# Daughter_Board.net
KiCad netlist of a schematic drawn in EAGLE
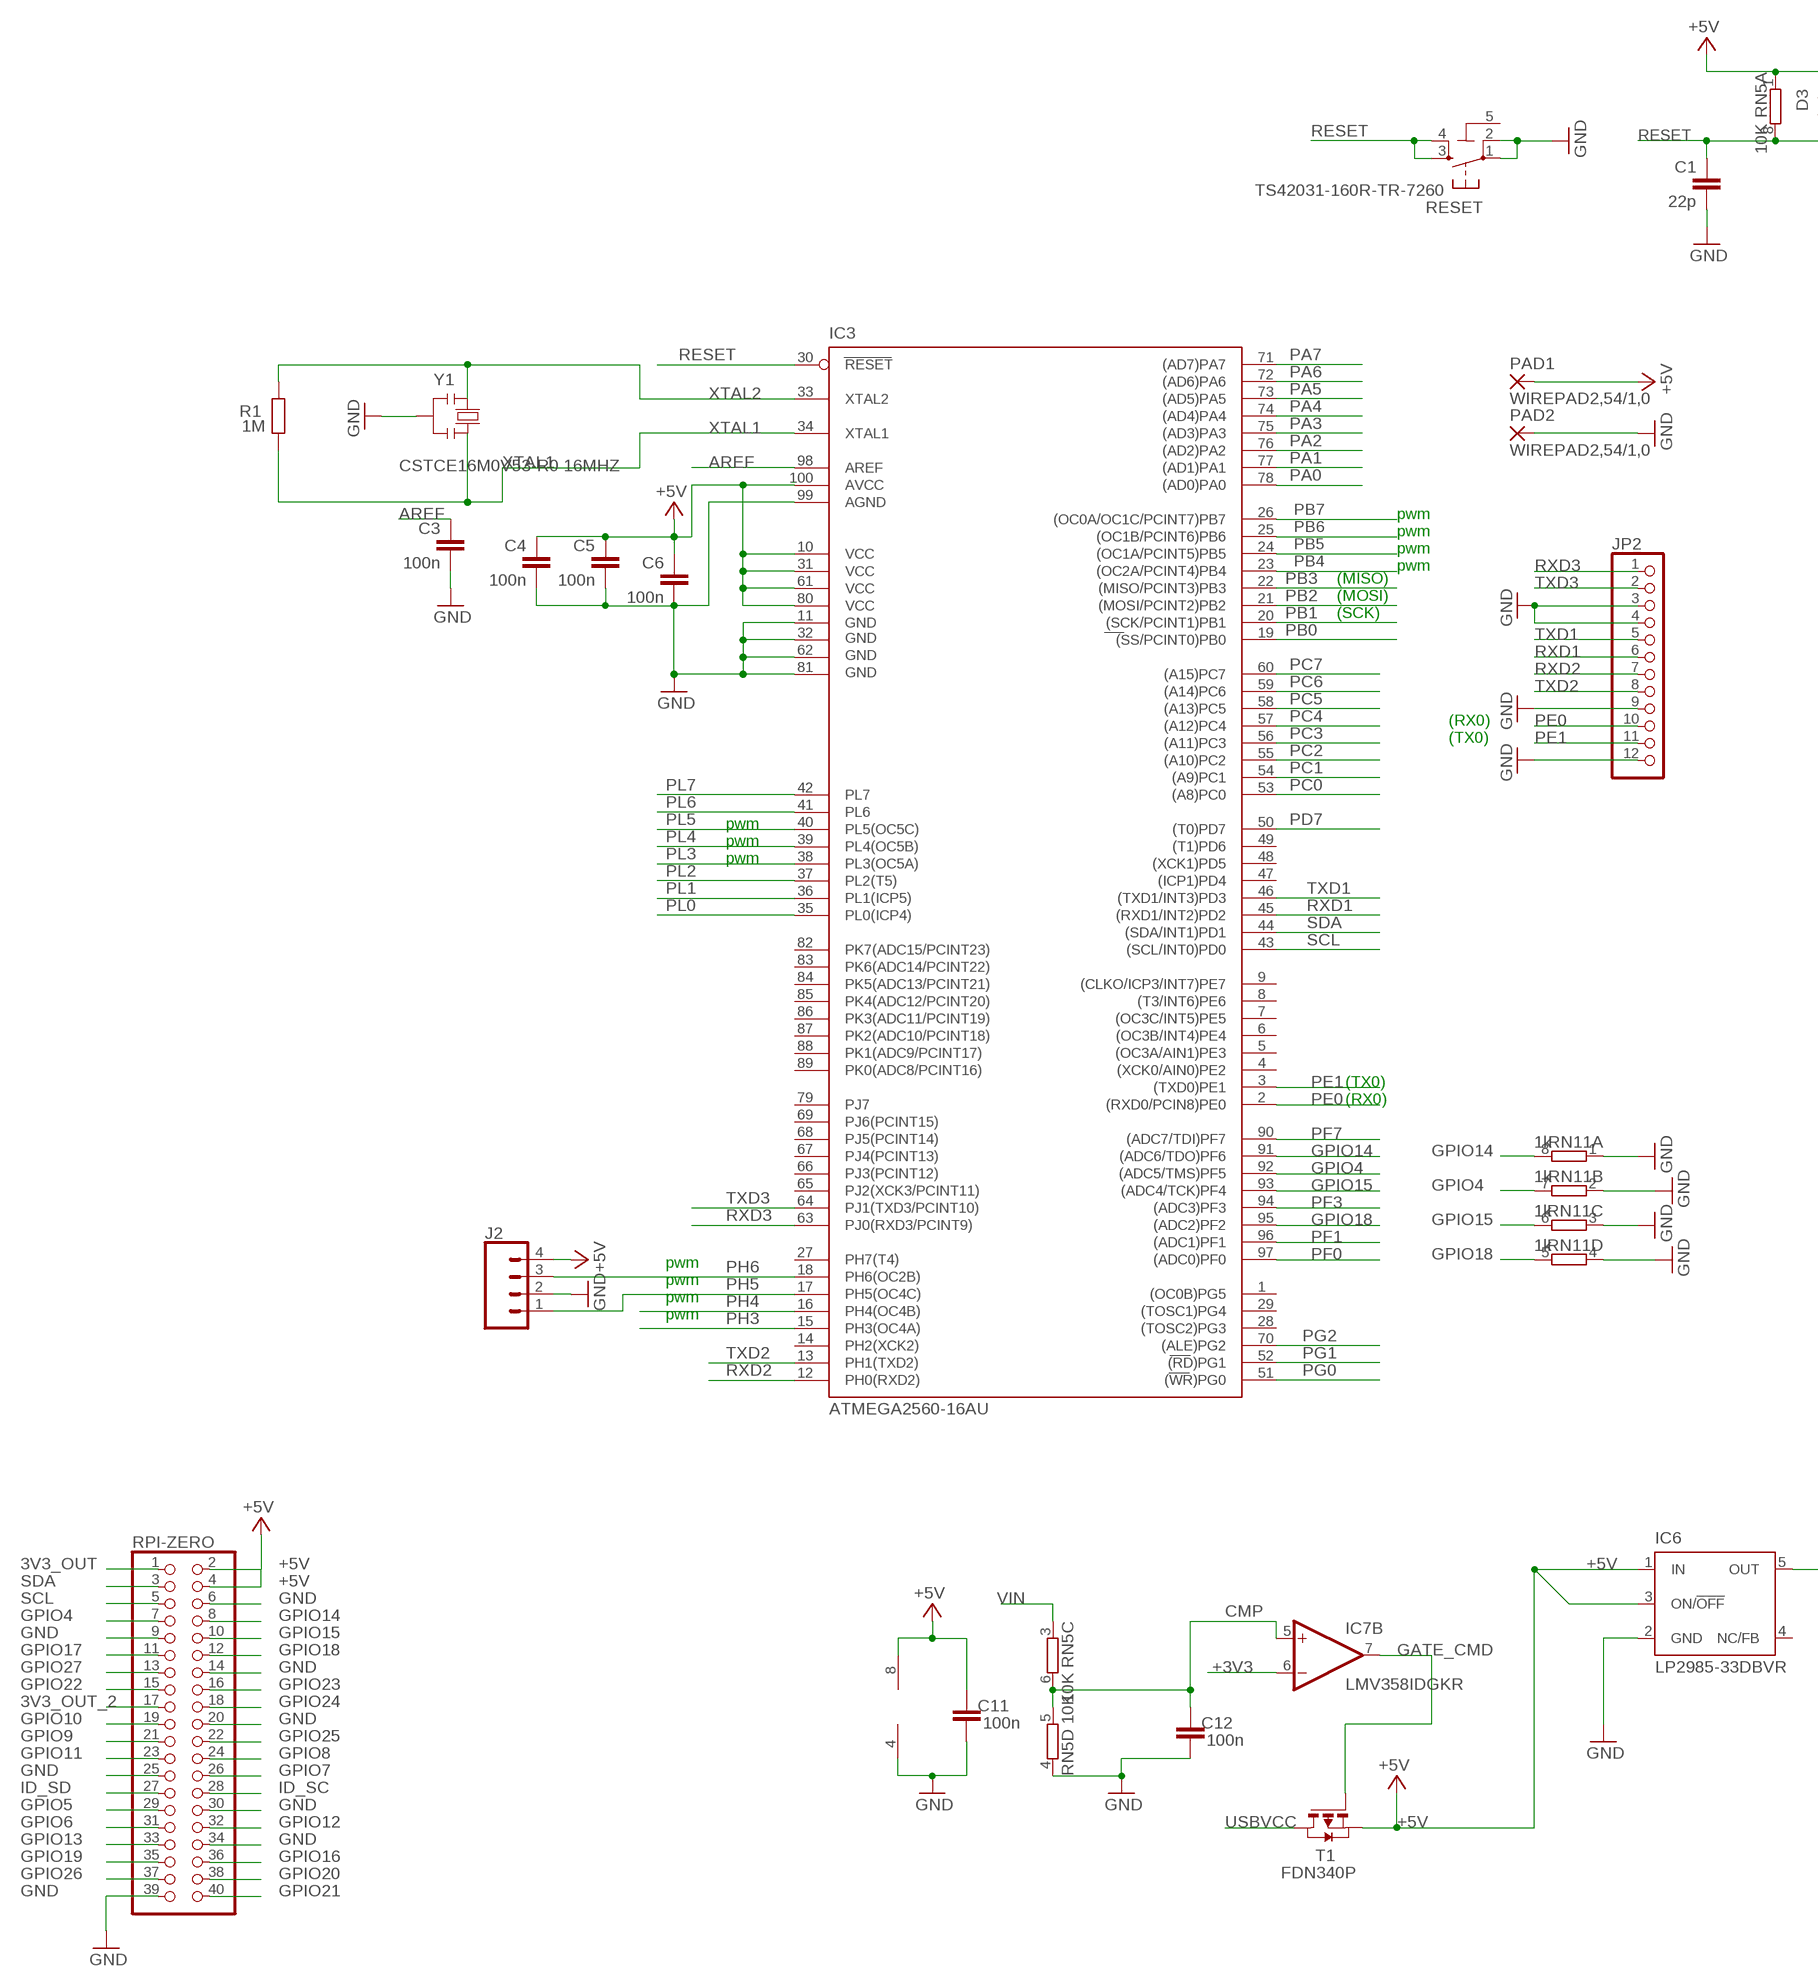
[diagram p0: schematic, sheet 1, part 1 of 2]
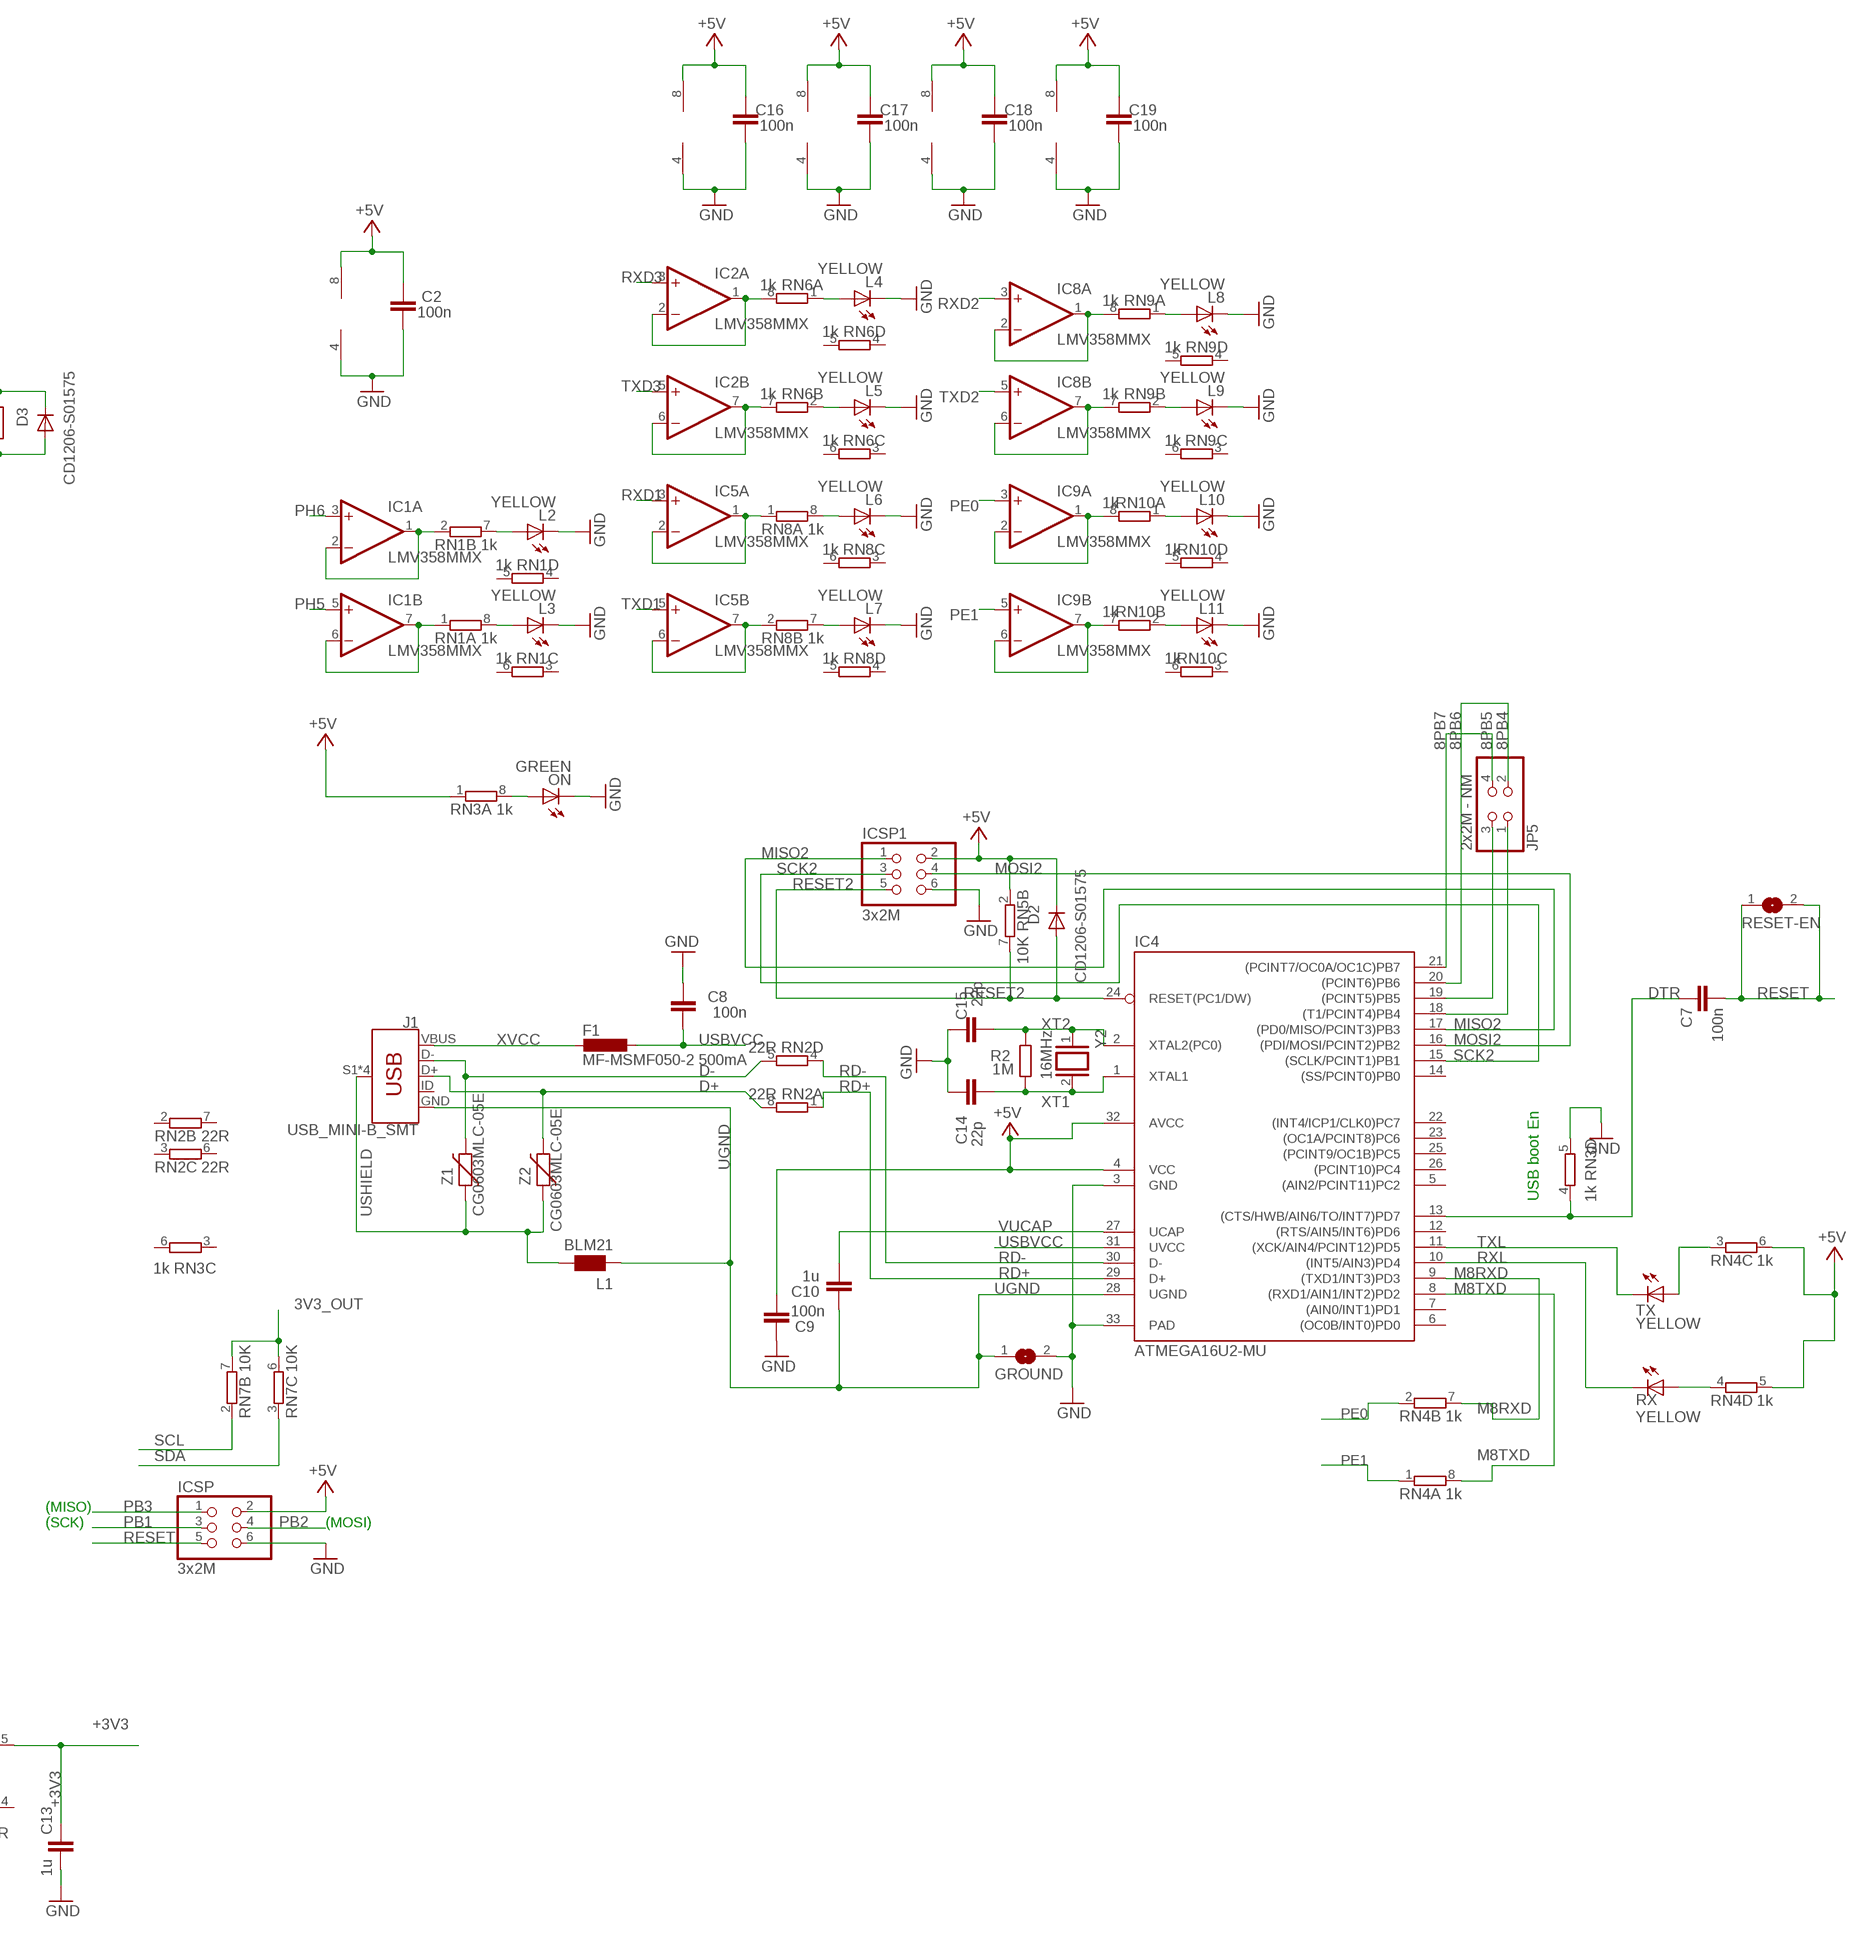
[diagram p1: schematic, sheet 1, part 2 of 2]

(export (version "E")
  (design (tool "Eeschema 10.0.6"))
  (components
    (comp (ref "C1")
      (value "22p")
      (footprint "eagle-import:C0603-ROUND")
      (libsource (lib "eagle-import") (part "C-EU0603-RND"))
    )
    (comp (ref "C2")
      (value "100n")
      (footprint "eagle-import:C0603-ROUND")
      (libsource (lib "eagle-import") (part "C-EU0603-RND"))
    )
    (comp (ref "C3")
      (value "100n")
      (footprint "eagle-import:C0603-ROUND")
      (libsource (lib "eagle-import") (part "C-EU0603-RND"))
    )
    (comp (ref "C4")
      (value "100n")
      (footprint "eagle-import:C0603-ROUND")
      (libsource (lib "eagle-import") (part "C-EU0603-RND"))
    )
    (comp (ref "C5")
      (value "100n")
      (footprint "eagle-import:C0603-ROUND")
      (libsource (lib "eagle-import") (part "C-EU0603-RND"))
    )
    (comp (ref "C6")
      (value "100n")
      (footprint "eagle-import:C0603-ROUND")
      (libsource (lib "eagle-import") (part "C-EU0603-RND"))
    )
    (comp (ref "C7")
      (value "100n")
      (footprint "eagle-import:C0603-ROUND")
      (libsource (lib "eagle-import") (part "C-EU0603-RND"))
    )
    (comp (ref "C8")
      (value "100n")
      (footprint "eagle-import:C0603-ROUND")
      (libsource (lib "eagle-import") (part "C-EU0603-RND"))
    )
    (comp (ref "C9")
      (value "100n")
      (footprint "eagle-import:C0603-ROUND")
      (libsource (lib "eagle-import") (part "C-EU0603-RND"))
    )
    (comp (ref "C10")
      (value "1u")
      (footprint "eagle-import:C0603-ROUND")
      (libsource (lib "eagle-import") (part "C-EU0603-RND"))
    )
    (comp (ref "C11")
      (value "100n")
      (footprint "eagle-import:C0603-ROUND")
      (libsource (lib "eagle-import") (part "C-EU0603-RND"))
    )
    (comp (ref "C12")
      (value "100n")
      (footprint "eagle-import:C0603-ROUND")
      (libsource (lib "eagle-import") (part "C-EU0603-RND"))
    )
    (comp (ref "C13")
      (value "1u")
      (footprint "eagle-import:C0603-ROUND")
      (libsource (lib "eagle-import") (part "C-EU0603-RND"))
    )
    (comp (ref "C14")
      (value "22p")
      (footprint "eagle-import:C0603-ROUND")
      (libsource (lib "eagle-import") (part "C-EU0603-RND"))
    )
    (comp (ref "C15")
      (value "22p")
      (footprint "eagle-import:C0603-ROUND")
      (libsource (lib "eagle-import") (part "C-EU0603-RND"))
    )
    (comp (ref "C16")
      (value "100n")
      (footprint "eagle-import:C0603-ROUND")
      (libsource (lib "eagle-import") (part "C-EU0603-RND"))
    )
    (comp (ref "C17")
      (value "100n")
      (footprint "eagle-import:C0603-ROUND")
      (libsource (lib "eagle-import") (part "C-EU0603-RND"))
    )
    (comp (ref "C18")
      (value "100n")
      (footprint "eagle-import:C0603-ROUND")
      (libsource (lib "eagle-import") (part "C-EU0603-RND"))
    )
    (comp (ref "C19")
      (value "100n")
      (footprint "eagle-import:C0603-ROUND")
      (libsource (lib "eagle-import") (part "C-EU0603-RND"))
    )
    (comp (ref "D2")
      (value "CD1206-S01575")
      (footprint "eagle-import:MINIMELF")
      (libsource (lib "eagle-import") (part "DIODE-MINIMELF"))
    )
    (comp (ref "D3")
      (value "CD1206-S01575")
      (footprint "eagle-import:MINIMELF")
      (libsource (lib "eagle-import") (part "DIODE-MINIMELF"))
    )
    (comp (ref "F1")
      (value "MF-MSMF050-2 500mA")
      (footprint "eagle-import:L1812")
      (libsource (lib "eagle-import") (part "L-EUL1812"))
    )
    (comp (ref "GROUND")
      (value "SJ")
      (footprint "eagle-import:SJ")
      (libsource (lib "eagle-import") (part "SJ"))
    )
    (comp (ref "IC1")
      (value "LMV358MMX")
      (footprint "eagle-import:MSOP08")
      (libsource (lib "eagle-import") (part "linear_262_LMV358?MMX"))
    )
    (comp (ref "IC2")
      (value "LMV358MMX")
      (footprint "eagle-import:MSOP08")
      (libsource (lib "eagle-import") (part "linear_262_LMV358?MMX"))
    )
    (comp (ref "IC3")
      (value "ATMEGA2560-16AU")
      (footprint "eagle-import:TQFP100")
      (libsource (lib "eagle-import") (part "ATMEGA2560AU2560-16"))
    )
    (comp (ref "IC4")
      (value "ATMEGA16U2-MU")
      (footprint "eagle-import:MLF32")
      (libsource (lib "eagle-import") (part "ATMEGA16U2-MU"))
    )
    (comp (ref "IC5")
      (value "LMV358MMX")
      (footprint "eagle-import:MSOP08")
      (libsource (lib "eagle-import") (part "linear_262_LMV358?MMX"))
    )
    (comp (ref "IC6")
      (value "LP2985-33DBVR")
      (footprint "eagle-import:SOT23-DBV")
      (libsource (lib "eagle-import") (part "LP2985-XXDBVR33"))
    )
    (comp (ref "IC7")
      (value "LMV358IDGKR")
      (footprint "eagle-import:MSOP08")
      (libsource (lib "eagle-import") (part "LMV358?MMX"))
    )
    (comp (ref "IC8")
      (value "LMV358MMX")
      (footprint "eagle-import:MSOP08")
      (libsource (lib "eagle-import") (part "linear_262_LMV358?MMX"))
    )
    (comp (ref "IC9")
      (value "LMV358MMX")
      (footprint "eagle-import:MSOP08")
      (libsource (lib "eagle-import") (part "linear_262_LMV358?MMX"))
    )
    (comp (ref "ICSP")
      (value "3x2M")
      (footprint "eagle-import:2X03")
      (libsource (lib "eagle-import") (part "PINHD-2X3"))
    )
    (comp (ref "ICSP1")
      (value "3x2M")
      (footprint "eagle-import:2X03")
      (libsource (lib "eagle-import") (part "PINHD-2X3"))
    )
    (comp (ref "J1")
      (value "USB_MINI-B_SMT")
      (footprint "eagle-import:USB-MINIB")
      (libsource (lib "eagle-import") (part "USB_MINI-B_SMT"))
    )
    (comp (ref "J2")
      (value "CONN_04")
      (footprint "eagle-import:1X04")
      (libsource (lib "eagle-import") (part "CONN_04"))
    )
    (comp (ref "JP2")
      (value "PINHD-1X12-CB")
      (footprint "eagle-import:1X12-CB")
      (libsource (lib "eagle-import") (part "PINHD-1X12-CB"))
    )
    (comp (ref "JP5")
      (value "2x2M - NM")
      (footprint "eagle-import:2X02")
      (libsource (lib "eagle-import") (part "PINHD-2X2"))
    )
    (comp (ref "L1")
      (value "BLM21")
      (footprint "eagle-import:0805")
      (libsource (lib "eagle-import") (part "WE-CBF_0805"))
    )
    (comp (ref "L2")
      (value "YELLOW")
      (footprint "eagle-import:CHIP-LED0805")
      (libsource (lib "eagle-import") (part "LEDCHIP-LED0805"))
    )
    (comp (ref "L3")
      (value "YELLOW")
      (footprint "eagle-import:CHIP-LED0805")
      (libsource (lib "eagle-import") (part "LEDCHIP-LED0805"))
    )
    (comp (ref "L4")
      (value "YELLOW")
      (footprint "eagle-import:CHIP-LED0805")
      (libsource (lib "eagle-import") (part "LEDCHIP-LED0805"))
    )
    (comp (ref "L5")
      (value "YELLOW")
      (footprint "eagle-import:CHIP-LED0805")
      (libsource (lib "eagle-import") (part "LEDCHIP-LED0805"))
    )
    (comp (ref "L6")
      (value "YELLOW")
      (footprint "eagle-import:CHIP-LED0805")
      (libsource (lib "eagle-import") (part "LEDCHIP-LED0805"))
    )
    (comp (ref "L7")
      (value "YELLOW")
      (footprint "eagle-import:CHIP-LED0805")
      (libsource (lib "eagle-import") (part "LEDCHIP-LED0805"))
    )
    (comp (ref "L8")
      (value "YELLOW")
      (footprint "eagle-import:CHIP-LED0805")
      (libsource (lib "eagle-import") (part "LEDCHIP-LED0805"))
    )
    (comp (ref "L9")
      (value "YELLOW")
      (footprint "eagle-import:CHIP-LED0805")
      (libsource (lib "eagle-import") (part "LEDCHIP-LED0805"))
    )
    (comp (ref "L10")
      (value "YELLOW")
      (footprint "eagle-import:CHIP-LED0805")
      (libsource (lib "eagle-import") (part "LEDCHIP-LED0805"))
    )
    (comp (ref "L11")
      (value "YELLOW")
      (footprint "eagle-import:CHIP-LED0805")
      (libsource (lib "eagle-import") (part "LEDCHIP-LED0805"))
    )
    (comp (ref "ON")
      (value "GREEN")
      (footprint "eagle-import:CHIP-LED0805")
      (libsource (lib "eagle-import") (part "LEDCHIP-LED0805"))
    )
    (comp (ref "PAD1")
      (value "WIREPAD2,54/1,0")
      (footprint "eagle-import:2,54_1,0")
      (libsource (lib "eagle-import") (part "WIREPAD2,54/1,0"))
    )
    (comp (ref "PAD2")
      (value "WIREPAD2,54/1,0")
      (footprint "eagle-import:2,54_1,0")
      (libsource (lib "eagle-import") (part "WIREPAD2,54/1,0"))
    )
    (comp (ref "R1")
      (value "1M")
      (footprint "eagle-import:R0603-ROUND")
      (libsource (lib "eagle-import") (part "R-EU_R0603"))
    )
    (comp (ref "R2")
      (value "1M")
      (footprint "eagle-import:R0603-ROUND")
      (libsource (lib "eagle-import") (part "R-EU_R0603"))
    )
    (comp (ref "RESET")
      (value "TS42031-160R-TR-7260")
      (footprint "eagle-import:TS42")
      (libsource (lib "eagle-import") (part "TS42"))
    )
    (comp (ref "RESET-EN")
      (value "SJ")
      (footprint "eagle-import:SJ")
      (libsource (lib "eagle-import") (part "SJ"))
    )
    (comp (ref "RN1")
      (value "1k")
      (footprint "eagle-import:CAY16")
      (libsource (lib "eagle-import") (part "4R-NCAY16"))
    )
    (comp (ref "RN2")
      (value "22R")
      (footprint "eagle-import:CAY16")
      (libsource (lib "eagle-import") (part "4R-NCAY16"))
    )
    (comp (ref "RN3")
      (value "1k")
      (footprint "eagle-import:CAY16")
      (libsource (lib "eagle-import") (part "4R-NCAY16"))
    )
    (comp (ref "RN4")
      (value "1k")
      (footprint "eagle-import:CAY16")
      (libsource (lib "eagle-import") (part "4R-NCAY16"))
    )
    (comp (ref "RN5")
      (value "10K")
      (footprint "eagle-import:CAT16")
      (libsource (lib "eagle-import") (part "4R-NCAT16"))
    )
    (comp (ref "RN6")
      (value "1k")
      (footprint "eagle-import:CAY16")
      (libsource (lib "eagle-import") (part "4R-NCAY16"))
    )
    (comp (ref "RN7")
      (value "10K")
      (footprint "eagle-import:CAT16")
      (libsource (lib "eagle-import") (part "4R-NCAT16"))
    )
    (comp (ref "RN8")
      (value "1k")
      (footprint "eagle-import:CAY16")
      (libsource (lib "eagle-import") (part "4R-NCAY16"))
    )
    (comp (ref "RN9")
      (value "1k")
      (footprint "eagle-import:CAY16")
      (libsource (lib "eagle-import") (part "4R-NCAY16"))
    )
    (comp (ref "RN10")
      (value "1k")
      (footprint "eagle-import:CAY16")
      (libsource (lib "eagle-import") (part "4R-NCAY16"))
    )
    (comp (ref "RN11")
      (value "1k")
      (footprint "eagle-import:CAY16")
      (libsource (lib "eagle-import") (part "4R-NCAY16"))
    )
    (comp (ref "RPI-ZERO")
      (value "PINHD-2X20")
      (footprint "eagle-import:2X20")
      (libsource (lib "eagle-import") (part "PINHD-2X20"))
    )
    (comp (ref "RX")
      (value "YELLOW")
      (footprint "eagle-import:CHIP-LED0805")
      (libsource (lib "eagle-import") (part "LEDCHIP-LED0805"))
    )
    (comp (ref "T1")
      (value "FDN340P")
      (footprint "eagle-import:SOT-23")
      (libsource (lib "eagle-import") (part "PMOSSOT23"))
    )
    (comp (ref "TX")
      (value "YELLOW")
      (footprint "eagle-import:CHIP-LED0805")
      (libsource (lib "eagle-import") (part "LEDCHIP-LED0805"))
    )
    (comp (ref "Y1")
      (value "CSTCE16M0V53-R0 16MHZ")
      (footprint "eagle-import:RESONATOR")
      (libsource (lib "eagle-import") (part "RESONATORMU"))
    )
    (comp (ref "Y2")
      (value "16MHz")
      (footprint "eagle-import:QS")
      (libsource (lib "eagle-import") (part "XTAL/S"))
    )
    (comp (ref "Z1")
      (value "CG0603MLC-05E")
      (footprint "eagle-import:CT_CN0603")
      (libsource (lib "eagle-import") (part "VARISTORCN0603"))
    )
    (comp (ref "Z2")
      (value "CG0603MLC-05E")
      (footprint "eagle-import:CT_CN0603")
      (libsource (lib "eagle-import") (part "VARISTORCN0603"))
    )
  )
  (nets
    (net (code "1") (name "+5V") (class "Default")
      (node (ref "C11") (pin "2") (pinfunction "2_2") (pintype "passive"))
      (node (ref "C16") (pin "2") (pinfunction "2_2") (pintype "passive"))
      (node (ref "C17") (pin "2") (pinfunction "2_2") (pintype "passive"))
      (node (ref "C18") (pin "2") (pinfunction "2_2") (pintype "passive"))
      (node (ref "C19") (pin "2") (pinfunction "2_2") (pintype "passive"))
      (node (ref "C2") (pin "2") (pinfunction "2_2") (pintype "passive"))
      (node (ref "C4") (pin "1") (pinfunction "1_1") (pintype "passive"))
      (node (ref "C5") (pin "1") (pinfunction "1_1") (pintype "passive"))
      (node (ref "C6") (pin "1") (pinfunction "1_1") (pintype "passive"))
      (node (ref "C9") (pin "1") (pinfunction "1_1") (pintype "passive"))
      (node (ref "D2") (pin "C") (pinfunction "C_C") (pintype "passive"))
      (node (ref "D3") (pin "C") (pinfunction "C_C") (pintype "passive"))
      (node (ref "IC1") (pin "8") (pinfunction "V+_8") (pintype "power_in"))
      (node (ref "IC2") (pin "8") (pinfunction "V+_8") (pintype "power_in"))
      (node (ref "IC3") (pin "10") (pinfunction "VCC_10") (pintype "power_in"))
      (node (ref "IC3") (pin "100") (pinfunction "AVCC_100") (pintype "power_in"))
      (node (ref "IC3") (pin "31") (pinfunction "VCC1_31") (pintype "power_in"))
      (node (ref "IC3") (pin "61") (pinfunction "VCC2_61") (pintype "power_in"))
      (node (ref "IC3") (pin "80") (pinfunction "VCC3_80") (pintype "power_in"))
      (node (ref "IC4") (pin "32") (pinfunction "AVCC_32") (pintype "power_in"))
      (node (ref "IC4") (pin "4") (pinfunction "VCC_4") (pintype "power_in"))
      (node (ref "IC5") (pin "8") (pinfunction "V+_8") (pintype "power_in"))
      (node (ref "IC6") (pin "1") (pinfunction "IN_1") (pintype "input"))
      (node (ref "IC6") (pin "3") (pinfunction "ON/~{OFF}_3") (pintype "input"))
      (node (ref "IC7") (pin "8") (pinfunction "V+_8") (pintype "power_in"))
      (node (ref "IC8") (pin "8") (pinfunction "V+_8") (pintype "power_in"))
      (node (ref "IC9") (pin "8") (pinfunction "V+_8") (pintype "power_in"))
      (node (ref "ICSP") (pin "2") (pinfunction "2_2") (pintype "passive"))
      (node (ref "ICSP1") (pin "2") (pinfunction "2_2") (pintype "passive"))
      (node (ref "J2") (pin "4") (pinfunction "4_4") (pintype "passive"))
      (node (ref "PAD1") (pin "1") (pinfunction "P_1") (pintype "passive"))
      (node (ref "RN3") (pin "1") (pinfunction "1_1") (pintype "passive"))
      (node (ref "RN4") (pin "5") (pinfunction "2_5") (pintype "passive"))
      (node (ref "RN4") (pin "6") (pinfunction "2_6") (pintype "passive"))
      (node (ref "RN5") (pin "1") (pinfunction "1_1") (pintype "passive"))
      (node (ref "RN5") (pin "2") (pinfunction "1_2") (pintype "passive"))
      (node (ref "RPI-ZERO") (pin "2") (pinfunction "2_2") (pintype "passive"))
      (node (ref "RPI-ZERO") (pin "4") (pinfunction "4_4") (pintype "passive"))
      (node (ref "T1") (pin "2") (pinfunction "S_2") (pintype "passive"))
    )
    (net (code "2") (name "/+3V3") (class "Default")
      (node (ref "C13") (pin "2") (pinfunction "2_2") (pintype "passive"))
      (node (ref "IC6") (pin "5") (pinfunction "OUT_5") (pintype "passive"))
      (node (ref "IC7") (pin "6") (pinfunction "-IN_6") (pintype "input"))
    )
    (net (code "3") (name "/3V3_OUT") (class "Default")
      (node (ref "RN7") (pin "6") (pinfunction "2_6") (pintype "passive"))
      (node (ref "RN7") (pin "7") (pinfunction "2_7") (pintype "passive"))
      (node (ref "RPI-ZERO") (pin "1") (pinfunction "1_1") (pintype "passive"))
    )
    (net (code "4") (name "/3V3_OUT_2") (class "Default")
      (node (ref "RPI-ZERO") (pin "17") (pinfunction "17_17") (pintype "passive"))
    )
    (net (code "5") (name "/5-GND") (class "Default")
      (node (ref "RESET") (pin "5") (pinfunction "5-GND_5") (pintype "power_in"))
    )
    (net (code "6") (name "/8PB4") (class "Default")
      (node (ref "IC4") (pin "18") (pinfunction "(T1/PCINT4)PB4_18") (pintype "bidirectional"))
      (node (ref "JP5") (pin "1") (pinfunction "1_1") (pintype "passive"))
    )
    (net (code "7") (name "/8PB5") (class "Default")
      (node (ref "IC4") (pin "19") (pinfunction "(PCINT5)PB5_19") (pintype "bidirectional"))
      (node (ref "JP5") (pin "3") (pinfunction "3_3") (pintype "passive"))
    )
    (net (code "8") (name "/8PB6") (class "Default")
      (node (ref "IC4") (pin "20") (pinfunction "(PCINT6)PB6_20") (pintype "bidirectional"))
      (node (ref "JP5") (pin "2") (pinfunction "2_2") (pintype "passive"))
    )
    (net (code "9") (name "/8PB7") (class "Default")
      (node (ref "IC4") (pin "21") (pinfunction "(PCINT7/OC0A/OC1C)PB7_21") (pintype "bidirectional"))
      (node (ref "JP5") (pin "4") (pinfunction "4_4") (pintype "passive"))
    )
    (net (code "10") (name "/AREF") (class "Default")
      (node (ref "C3") (pin "1") (pinfunction "1_1") (pintype "passive"))
      (node (ref "IC3") (pin "98") (pinfunction "AREF_98") (pintype "bidirectional"))
    )
    (net (code "11") (name "/CMP") (class "Default")
      (node (ref "C12") (pin "2") (pinfunction "2_2") (pintype "passive"))
      (node (ref "IC7") (pin "5") (pinfunction "+IN_5") (pintype "input"))
      (node (ref "RN5") (pin "5") (pinfunction "2_5") (pintype "passive"))
      (node (ref "RN5") (pin "6") (pinfunction "2_6") (pintype "passive"))
    )
    (net (code "12") (name "/D+") (class "Default")
      (node (ref "J1") (pin "D+") (pinfunction "D+_D+") (pintype "bidirectional"))
      (node (ref "RN2") (pin "8") (pinfunction "2_8") (pintype "passive"))
      (node (ref "Z2") (pin "2") (pinfunction "2_2") (pintype "passive"))
    )
    (net (code "13") (name "/D-") (class "Default")
      (node (ref "J1") (pin "D-") (pinfunction "D-_D-") (pintype "bidirectional"))
      (node (ref "RN2") (pin "5") (pinfunction "2_5") (pintype "passive"))
      (node (ref "Z1") (pin "2") (pinfunction "2_2") (pintype "passive"))
    )
    (net (code "14") (name "/DTR") (class "Default")
      (node (ref "C7") (pin "1") (pinfunction "1_1") (pintype "passive"))
      (node (ref "IC4") (pin "13") (pinfunction "(CTS/HWB/AIN6/TO/INT7)PD7_13") (pintype "bidirectional"))
      (node (ref "RN3") (pin "4") (pinfunction "1_4") (pintype "passive"))
    )
    (net (code "15") (name "/GATE_CMD") (class "Default")
      (node (ref "IC7") (pin "7") (pinfunction "OUT_7") (pintype "output"))
      (node (ref "T1") (pin "3") (pinfunction "G_3") (pintype "passive"))
    )
    (net (code "16") (name "/GPIO4") (class "Default")
      (node (ref "IC3") (pin "92") (pinfunction "(ADC5/TMS)PF5_92") (pintype "bidirectional"))
      (node (ref "RN11") (pin "7") (pinfunction "2_7") (pintype "passive"))
      (node (ref "RPI-ZERO") (pin "7") (pinfunction "7_7") (pintype "passive"))
    )
    (net (code "17") (name "/GPIO5") (class "Default")
      (node (ref "RPI-ZERO") (pin "29") (pinfunction "29_29") (pintype "passive"))
    )
    (net (code "18") (name "/GPIO6") (class "Default")
      (node (ref "RPI-ZERO") (pin "31") (pinfunction "31_31") (pintype "passive"))
    )
    (net (code "19") (name "/GPIO7") (class "Default")
      (node (ref "RPI-ZERO") (pin "26") (pinfunction "26_26") (pintype "passive"))
    )
    (net (code "20") (name "/GPIO8") (class "Default")
      (node (ref "RPI-ZERO") (pin "24") (pinfunction "24_24") (pintype "passive"))
    )
    (net (code "21") (name "/GPIO9") (class "Default")
      (node (ref "RPI-ZERO") (pin "21") (pinfunction "21_21") (pintype "passive"))
    )
    (net (code "22") (name "/GPIO10") (class "Default")
      (node (ref "RPI-ZERO") (pin "19") (pinfunction "19_19") (pintype "passive"))
    )
    (net (code "23") (name "/GPIO11") (class "Default")
      (node (ref "RPI-ZERO") (pin "23") (pinfunction "23_23") (pintype "passive"))
    )
    (net (code "24") (name "/GPIO12") (class "Default")
      (node (ref "RPI-ZERO") (pin "32") (pinfunction "32_32") (pintype "passive"))
    )
    (net (code "25") (name "/GPIO13") (class "Default")
      (node (ref "RPI-ZERO") (pin "33") (pinfunction "33_33") (pintype "passive"))
    )
    (net (code "26") (name "/GPIO14") (class "Default")
      (node (ref "IC3") (pin "91") (pinfunction "(ADC6/TDO)PF6_91") (pintype "bidirectional"))
      (node (ref "RN11") (pin "8") (pinfunction "2_8") (pintype "passive"))
      (node (ref "RPI-ZERO") (pin "8") (pinfunction "8_8") (pintype "passive"))
    )
    (net (code "27") (name "/GPIO15") (class "Default")
      (node (ref "IC3") (pin "93") (pinfunction "(ADC4/TCK)PF4_93") (pintype "bidirectional"))
      (node (ref "RN11") (pin "6") (pinfunction "2_6") (pintype "passive"))
      (node (ref "RPI-ZERO") (pin "10") (pinfunction "10_10") (pintype "passive"))
    )
    (net (code "28") (name "/GPIO16") (class "Default")
      (node (ref "RPI-ZERO") (pin "36") (pinfunction "36_36") (pintype "passive"))
    )
    (net (code "29") (name "/GPIO17") (class "Default")
      (node (ref "RPI-ZERO") (pin "11") (pinfunction "11_11") (pintype "passive"))
    )
    (net (code "30") (name "/GPIO18") (class "Default")
      (node (ref "IC3") (pin "95") (pinfunction "(ADC2)PF2_95") (pintype "bidirectional"))
      (node (ref "RN11") (pin "5") (pinfunction "2_5") (pintype "passive"))
      (node (ref "RPI-ZERO") (pin "12") (pinfunction "12_12") (pintype "passive"))
    )
    (net (code "31") (name "/GPIO19") (class "Default")
      (node (ref "RPI-ZERO") (pin "35") (pinfunction "35_35") (pintype "passive"))
    )
    (net (code "32") (name "/GPIO20") (class "Default")
      (node (ref "RPI-ZERO") (pin "38") (pinfunction "38_38") (pintype "passive"))
    )
    (net (code "33") (name "/GPIO21") (class "Default")
      (node (ref "RPI-ZERO") (pin "40") (pinfunction "40_40") (pintype "passive"))
    )
    (net (code "34") (name "/GPIO22") (class "Default")
      (node (ref "RPI-ZERO") (pin "15") (pinfunction "15_15") (pintype "passive"))
    )
    (net (code "35") (name "/GPIO23") (class "Default")
      (node (ref "RPI-ZERO") (pin "16") (pinfunction "16_16") (pintype "passive"))
    )
    (net (code "36") (name "/GPIO24") (class "Default")
      (node (ref "RPI-ZERO") (pin "18") (pinfunction "18_18") (pintype "passive"))
    )
    (net (code "37") (name "/GPIO25") (class "Default")
      (node (ref "RPI-ZERO") (pin "22") (pinfunction "22_22") (pintype "passive"))
    )
    (net (code "38") (name "/GPIO26") (class "Default")
      (node (ref "RPI-ZERO") (pin "37") (pinfunction "37_37") (pintype "passive"))
    )
    (net (code "39") (name "/GPIO27") (class "Default")
      (node (ref "RPI-ZERO") (pin "13") (pinfunction "13_13") (pintype "passive"))
    )
    (net (code "40") (name "/ID_SC") (class "Default")
      (node (ref "RPI-ZERO") (pin "28") (pinfunction "28_28") (pintype "passive"))
    )
    (net (code "41") (name "/ID_SD") (class "Default")
      (node (ref "RPI-ZERO") (pin "27") (pinfunction "27_27") (pintype "passive"))
    )
    (net (code "42") (name "/M8RXD") (class "Default")
      (node (ref "IC4") (pin "9") (pinfunction "(TXD1/INT3)PD3_9") (pintype "bidirectional"))
      (node (ref "RN4") (pin "7") (pinfunction "2_7") (pintype "passive"))
    )
    (net (code "43") (name "/M8TXD") (class "Default")
      (node (ref "IC4") (pin "8") (pinfunction "(RXD1/AIN1/INT2)PD2_8") (pintype "bidirectional"))
      (node (ref "RN4") (pin "8") (pinfunction "2_8") (pintype "passive"))
    )
    (net (code "44") (name "/MISO2") (class "Default")
      (node (ref "IC4") (pin "17") (pinfunction "(PD0/MISO/PCINT3)PB3_17") (pintype "bidirectional"))
      (node (ref "ICSP1") (pin "1") (pinfunction "1_1") (pintype "passive"))
    )
    (net (code "45") (name "/MOSI2") (class "Default")
      (node (ref "IC4") (pin "16") (pinfunction "(PDI/MOSI/PCINT2)PB2_16") (pintype "bidirectional"))
      (node (ref "ICSP1") (pin "4") (pinfunction "4_4") (pintype "passive"))
    )
    (net (code "46") (name "/PA0") (class "Default")
      (node (ref "IC3") (pin "78") (pinfunction "(AD0)PA0_78") (pintype "bidirectional"))
    )
    (net (code "47") (name "/PA1") (class "Default")
      (node (ref "IC3") (pin "77") (pinfunction "(AD1)PA1_77") (pintype "bidirectional"))
    )
    (net (code "48") (name "/PA2") (class "Default")
      (node (ref "IC3") (pin "76") (pinfunction "(AD2)PA2_76") (pintype "bidirectional"))
    )
    (net (code "49") (name "/PA3") (class "Default")
      (node (ref "IC3") (pin "75") (pinfunction "(AD3)PA3_75") (pintype "bidirectional"))
    )
    (net (code "50") (name "/PA4") (class "Default")
      (node (ref "IC3") (pin "74") (pinfunction "(AD4)PA4_74") (pintype "bidirectional"))
    )
    (net (code "51") (name "/PA5") (class "Default")
      (node (ref "IC3") (pin "73") (pinfunction "(AD5)PA5_73") (pintype "bidirectional"))
    )
    (net (code "52") (name "/PA6") (class "Default")
      (node (ref "IC3") (pin "72") (pinfunction "(AD6)PA6_72") (pintype "bidirectional"))
    )
    (net (code "53") (name "/PA7") (class "Default")
      (node (ref "IC3") (pin "71") (pinfunction "(AD7)PA7_71") (pintype "bidirectional"))
    )
    (net (code "54") (name "/PB0") (class "Default")
      (node (ref "IC3") (pin "19") (pinfunction "(SS/PCINT0)PB0_19") (pintype "bidirectional"))
    )
    (net (code "55") (name "/PB1") (class "Default")
      (node (ref "IC3") (pin "20") (pinfunction "(SCK/PCINT1)PB1_20") (pintype "bidirectional"))
      (node (ref "ICSP") (pin "3") (pinfunction "3_3") (pintype "passive"))
    )
    (net (code "56") (name "/PB2") (class "Default")
      (node (ref "IC3") (pin "21") (pinfunction "(MOSI/PCINT2)PB2_21") (pintype "bidirectional"))
      (node (ref "ICSP") (pin "4") (pinfunction "4_4") (pintype "passive"))
    )
    (net (code "57") (name "/PB3") (class "Default")
      (node (ref "IC3") (pin "22") (pinfunction "(MISO/PCINT3)PB3_22") (pintype "bidirectional"))
      (node (ref "ICSP") (pin "1") (pinfunction "1_1") (pintype "passive"))
    )
    (net (code "58") (name "/PB4") (class "Default")
      (node (ref "IC3") (pin "23") (pinfunction "(OC2A/PCINT4)PB4_23") (pintype "bidirectional"))
    )
    (net (code "59") (name "/PB5") (class "Default")
      (node (ref "IC3") (pin "24") (pinfunction "(OC1A/PCINT5)PB5_24") (pintype "bidirectional"))
    )
    (net (code "60") (name "/PB6") (class "Default")
      (node (ref "IC3") (pin "25") (pinfunction "(OC1B/PCINT6)PB6_25") (pintype "bidirectional"))
    )
    (net (code "61") (name "/PB7") (class "Default")
      (node (ref "IC3") (pin "26") (pinfunction "(OC0A/OC1C/PCINT7)PB7_26") (pintype "bidirectional"))
    )
    (net (code "62") (name "/PC0") (class "Default")
      (node (ref "IC3") (pin "53") (pinfunction "(A8)PC0_53") (pintype "bidirectional"))
    )
    (net (code "63") (name "/PC1") (class "Default")
      (node (ref "IC3") (pin "54") (pinfunction "(A9)PC1_54") (pintype "bidirectional"))
    )
    (net (code "64") (name "/PC2") (class "Default")
      (node (ref "IC3") (pin "55") (pinfunction "(A10)PC2_55") (pintype "bidirectional"))
    )
    (net (code "65") (name "/PC3") (class "Default")
      (node (ref "IC3") (pin "56") (pinfunction "(A11)PC3_56") (pintype "bidirectional"))
    )
    (net (code "66") (name "/PC4") (class "Default")
      (node (ref "IC3") (pin "57") (pinfunction "(A12)PC4_57") (pintype "bidirectional"))
    )
    (net (code "67") (name "/PC5") (class "Default")
      (node (ref "IC3") (pin "58") (pinfunction "(A13)PC5_58") (pintype "bidirectional"))
    )
    (net (code "68") (name "/PC6") (class "Default")
      (node (ref "IC3") (pin "59") (pinfunction "(A14)PC6_59") (pintype "bidirectional"))
    )
    (net (code "69") (name "/PC7") (class "Default")
      (node (ref "IC3") (pin "60") (pinfunction "(A15)PC7_60") (pintype "bidirectional"))
    )
    (net (code "70") (name "/PD7") (class "Default")
      (node (ref "IC3") (pin "50") (pinfunction "(T0)PD7_50") (pintype "bidirectional"))
    )
    (net (code "71") (name "/PE0") (class "Default")
      (node (ref "IC3") (pin "2") (pinfunction "(RXD0/PCIN8)PE0_2") (pintype "bidirectional"))
      (node (ref "IC9") (pin "3") (pinfunction "+IN_3") (pintype "input"))
      (node (ref "JP2") (pin "10") (pinfunction "10_10") (pintype "passive"))
      (node (ref "RN4") (pin "2") (pinfunction "1_2") (pintype "passive"))
    )
    (net (code "72") (name "/PE1") (class "Default")
      (node (ref "IC3") (pin "3") (pinfunction "(TXD0)PE1_3") (pintype "bidirectional"))
      (node (ref "IC9") (pin "5") (pinfunction "+IN_5") (pintype "input"))
      (node (ref "JP2") (pin "11") (pinfunction "11_11") (pintype "passive"))
      (node (ref "RN4") (pin "1") (pinfunction "1_1") (pintype "passive"))
    )
    (net (code "73") (name "/PF0") (class "Default")
      (node (ref "IC3") (pin "97") (pinfunction "(ADC0)PF0_97") (pintype "bidirectional"))
    )
    (net (code "74") (name "/PF1") (class "Default")
      (node (ref "IC3") (pin "96") (pinfunction "(ADC1)PF1_96") (pintype "bidirectional"))
    )
    (net (code "75") (name "/PF3") (class "Default")
      (node (ref "IC3") (pin "94") (pinfunction "(ADC3)PF3_94") (pintype "bidirectional"))
    )
    (net (code "76") (name "/PF7") (class "Default")
      (node (ref "IC3") (pin "90") (pinfunction "(ADC7/TDI)PF7_90") (pintype "bidirectional"))
    )
    (net (code "77") (name "/PG0") (class "Default")
      (node (ref "IC3") (pin "51") (pinfunction "(WR)PG0_51") (pintype "bidirectional"))
    )
    (net (code "78") (name "/PG1") (class "Default")
      (node (ref "IC3") (pin "52") (pinfunction "(RD)PG1_52") (pintype "bidirectional"))
    )
    (net (code "79") (name "/PG2") (class "Default")
      (node (ref "IC3") (pin "70") (pinfunction "(ALE)PG2_70") (pintype "bidirectional"))
    )
    (net (code "80") (name "/PH3") (class "Default")
      (node (ref "IC3") (pin "15") (pinfunction "PH3(OC4A)_15") (pintype "bidirectional"))
    )
    (net (code "81") (name "/PH4") (class "Default")
      (node (ref "IC3") (pin "16") (pinfunction "PH4(OC4B)_16") (pintype "bidirectional"))
    )
    (net (code "82") (name "/PH5") (class "Default")
      (node (ref "IC1") (pin "5") (pinfunction "+IN_5") (pintype "input"))
      (node (ref "IC3") (pin "17") (pinfunction "PH5(OC4C)_17") (pintype "bidirectional"))
      (node (ref "J2") (pin "1") (pinfunction "1_1") (pintype "passive"))
    )
    (net (code "83") (name "/PH6") (class "Default")
      (node (ref "IC1") (pin "3") (pinfunction "+IN_3") (pintype "input"))
      (node (ref "IC3") (pin "18") (pinfunction "PH6(OC2B)_18") (pintype "bidirectional"))
      (node (ref "J2") (pin "3") (pinfunction "3_3") (pintype "passive"))
    )
    (net (code "84") (name "/PL0") (class "Default")
      (node (ref "IC3") (pin "35") (pinfunction "PL0(ICP4)_35") (pintype "bidirectional"))
    )
    (net (code "85") (name "/PL1") (class "Default")
      (node (ref "IC3") (pin "36") (pinfunction "PL1(ICP5)_36") (pintype "bidirectional"))
    )
    (net (code "86") (name "/PL2") (class "Default")
      (node (ref "IC3") (pin "37") (pinfunction "PL2(T5)_37") (pintype "bidirectional"))
    )
    (net (code "87") (name "/PL3") (class "Default")
      (node (ref "IC3") (pin "38") (pinfunction "PL3(OC5A)_38") (pintype "bidirectional"))
    )
    (net (code "88") (name "/PL4") (class "Default")
      (node (ref "IC3") (pin "39") (pinfunction "PL4(OC5B)_39") (pintype "bidirectional"))
    )
    (net (code "89") (name "/PL5") (class "Default")
      (node (ref "IC3") (pin "40") (pinfunction "PL5(OC5C)_40") (pintype "bidirectional"))
    )
    (net (code "90") (name "/PL6") (class "Default")
      (node (ref "IC3") (pin "41") (pinfunction "PL6_41") (pintype "bidirectional"))
    )
    (net (code "91") (name "/PL7") (class "Default")
      (node (ref "IC3") (pin "42") (pinfunction "PL7_42") (pintype "bidirectional"))
    )
    (net (code "92") (name "/RD+") (class "Default")
      (node (ref "IC4") (pin "29") (pinfunction "D+_29") (pintype "bidirectional"))
      (node (ref "RN2") (pin "1") (pinfunction "1_1") (pintype "passive"))
    )
    (net (code "93") (name "/RD-") (class "Default")
      (node (ref "IC4") (pin "30") (pinfunction "D-_30") (pintype "bidirectional"))
      (node (ref "RN2") (pin "4") (pinfunction "1_4") (pintype "passive"))
    )
    (net (code "94") (name "/RESET") (class "Default")
      (node (ref "C1") (pin "1") (pinfunction "1_1") (pintype "passive"))
      (node (ref "C7") (pin "2") (pinfunction "2_2") (pintype "passive"))
      (node (ref "D3") (pin "A") (pinfunction "A_A") (pintype "passive"))
      (node (ref "IC3") (pin "30") (pinfunction "RESET_30") (pintype "input"))
      (node (ref "ICSP") (pin "5") (pinfunction "5_5") (pintype "passive"))
      (node (ref "RESET") (pin "3") (pinfunction "3_3") (pintype "passive"))
      (node (ref "RESET") (pin "4") (pinfunction "4_4") (pintype "passive"))
      (node (ref "RESET-EN") (pin "1") (pinfunction "1_1") (pintype "passive"))
      (node (ref "RESET-EN") (pin "2") (pinfunction "2_2") (pintype "passive"))
      (node (ref "RN5") (pin "8") (pinfunction "2_8") (pintype "passive"))
    )
    (net (code "95") (name "/RESET2") (class "Default")
      (node (ref "D2") (pin "A") (pinfunction "A_A") (pintype "passive"))
      (node (ref "IC4") (pin "24") (pinfunction "RESET(PC1/DW)_24") (pintype "input"))
      (node (ref "ICSP1") (pin "5") (pinfunction "5_5") (pintype "passive"))
      (node (ref "RN5") (pin "7") (pinfunction "2_7") (pintype "passive"))
    )
    (net (code "96") (name "/RXD1") (class "Default")
      (node (ref "IC3") (pin "45") (pinfunction "(RXD1/INT2)PD2_45") (pintype "bidirectional"))
      (node (ref "IC5") (pin "3") (pinfunction "+IN_3") (pintype "input"))
      (node (ref "JP2") (pin "6") (pinfunction "6_6") (pintype "passive"))
    )
    (net (code "97") (name "/RXD2") (class "Default")
      (node (ref "IC3") (pin "12") (pinfunction "PH0(RXD2)_12") (pintype "bidirectional"))
      (node (ref "IC8") (pin "3") (pinfunction "+IN_3") (pintype "input"))
      (node (ref "JP2") (pin "7") (pinfunction "7_7") (pintype "passive"))
    )
    (net (code "98") (name "/RXD3") (class "Default")
      (node (ref "IC2") (pin "3") (pinfunction "+IN_3") (pintype "input"))
      (node (ref "IC3") (pin "63") (pinfunction "PJ0(RXD3/PCINT9)_63") (pintype "bidirectional"))
      (node (ref "JP2") (pin "1") (pinfunction "1_1") (pintype "passive"))
    )
    (net (code "99") (name "/RXL") (class "Default")
      (node (ref "IC4") (pin "10") (pinfunction "(INT5/AIN3)PD4_10") (pintype "bidirectional"))
      (node (ref "RX") (pin "C") (pinfunction "C_C") (pintype "passive"))
    )
    (net (code "100") (name "/SCK2") (class "Default")
      (node (ref "IC4") (pin "15") (pinfunction "(SCLK/PCINT1)PB1_15") (pintype "bidirectional"))
      (node (ref "ICSP1") (pin "3") (pinfunction "3_3") (pintype "passive"))
    )
    (net (code "101") (name "/SCL") (class "Default")
      (node (ref "IC3") (pin "43") (pinfunction "(SCL/INT0)PD0_43") (pintype "bidirectional"))
      (node (ref "RN7") (pin "2") (pinfunction "1_2") (pintype "passive"))
      (node (ref "RPI-ZERO") (pin "5") (pinfunction "5_5") (pintype "passive"))
    )
    (net (code "102") (name "/SDA") (class "Default")
      (node (ref "IC3") (pin "44") (pinfunction "(SDA/INT1)PD1_44") (pintype "bidirectional"))
      (node (ref "RN7") (pin "3") (pinfunction "1_3") (pintype "passive"))
      (node (ref "RPI-ZERO") (pin "3") (pinfunction "3_3") (pintype "passive"))
    )
    (net (code "103") (name "/TXD1") (class "Default")
      (node (ref "IC3") (pin "46") (pinfunction "(TXD1/INT3)PD3_46") (pintype "bidirectional"))
      (node (ref "IC5") (pin "5") (pinfunction "+IN_5") (pintype "input"))
      (node (ref "JP2") (pin "5") (pinfunction "5_5") (pintype "passive"))
    )
    (net (code "104") (name "/TXD2") (class "Default")
      (node (ref "IC3") (pin "13") (pinfunction "PH1(TXD2)_13") (pintype "bidirectional"))
      (node (ref "IC8") (pin "5") (pinfunction "+IN_5") (pintype "input"))
      (node (ref "JP2") (pin "8") (pinfunction "8_8") (pintype "passive"))
    )
    (net (code "105") (name "/TXD3") (class "Default")
      (node (ref "IC2") (pin "5") (pinfunction "+IN_5") (pintype "input"))
      (node (ref "IC3") (pin "64") (pinfunction "PJ1(TXD3/PCINT10)_64") (pintype "bidirectional"))
      (node (ref "JP2") (pin "2") (pinfunction "2_2") (pintype "passive"))
    )
    (net (code "106") (name "/TXL") (class "Default")
      (node (ref "IC4") (pin "11") (pinfunction "(XCK/AIN4/PCINT12)PD5_11") (pintype "bidirectional"))
      (node (ref "TX") (pin "C") (pinfunction "C_C") (pintype "passive"))
    )
    (net (code "107") (name "/UGND") (class "Default")
      (node (ref "C10") (pin "2") (pinfunction "2_2") (pintype "passive"))
      (node (ref "GROUND") (pin "1") (pinfunction "1_1") (pintype "passive"))
      (node (ref "IC4") (pin "28") (pinfunction "UGND_28") (pintype "power_in"))
      (node (ref "J1") (pin "GND") (pinfunction "GND_GND") (pintype "power_in"))
      (node (ref "L1") (pin "1") (pinfunction "1_1") (pintype "passive"))
    )
    (net (code "108") (name "/USBVCC") (class "Default")
      (node (ref "C8") (pin "1") (pinfunction "1_1") (pintype "passive"))
      (node (ref "F1") (pin "1") (pinfunction "1_1") (pintype "passive"))
      (node (ref "IC4") (pin "31") (pinfunction "UVCC_31") (pintype "power_in"))
      (node (ref "T1") (pin "1") (pinfunction "D_1") (pintype "passive"))
    )
    (net (code "109") (name "/USHIELD") (class "Default")
      (node (ref "J1") (pin "S1") (pinfunction "SHIELD_S1") (pintype "bidirectional"))
      (node (ref "J1") (pin "S2") (pinfunction "SHIELD_S2") (pintype "bidirectional"))
      (node (ref "J1") (pin "S3") (pinfunction "SHIELD_S3") (pintype "bidirectional"))
      (node (ref "J1") (pin "S4") (pinfunction "SHIELD_S4") (pintype "bidirectional"))
      (node (ref "L1") (pin "2") (pinfunction "2_2") (pintype "passive"))
      (node (ref "Z1") (pin "1") (pinfunction "1_1") (pintype "passive"))
      (node (ref "Z2") (pin "1") (pinfunction "1_1") (pintype "passive"))
    )
    (net (code "110") (name "/VIN") (class "Default")
      (node (ref "RN5") (pin "3") (pinfunction "1_3") (pintype "passive"))
    )
    (net (code "111") (name "/VUCAP") (class "Default")
      (node (ref "C10") (pin "1") (pinfunction "1_1") (pintype "passive"))
      (node (ref "IC4") (pin "27") (pinfunction "UCAP_27") (pintype "passive"))
    )
    (net (code "112") (name "/XT1") (class "Default")
      (node (ref "C14") (pin "1") (pinfunction "1_1") (pintype "passive"))
      (node (ref "IC4") (pin "1") (pinfunction "XTAL1_1") (pintype "bidirectional"))
      (node (ref "R2") (pin "1") (pinfunction "1_1") (pintype "passive"))
      (node (ref "Y2") (pin "2") (pinfunction "2_2") (pintype "passive"))
    )
    (net (code "113") (name "/XT2") (class "Default")
      (node (ref "C15") (pin "1") (pinfunction "1_1") (pintype "passive"))
      (node (ref "IC4") (pin "2") (pinfunction "XTAL2(PC0)_2") (pintype "bidirectional"))
      (node (ref "R2") (pin "2") (pinfunction "2_2") (pintype "passive"))
      (node (ref "Y2") (pin "1") (pinfunction "1_1") (pintype "passive"))
    )
    (net (code "114") (name "/XTAL1") (class "Default")
      (node (ref "IC3") (pin "34") (pinfunction "XTAL1_34") (pintype "input"))
      (node (ref "R1") (pin "1") (pinfunction "1_1") (pintype "passive"))
      (node (ref "Y1") (pin "3") (pinfunction "3_3") (pintype "passive"))
    )
    (net (code "115") (name "/XTAL2") (class "Default")
      (node (ref "IC3") (pin "33") (pinfunction "XTAL2_33") (pintype "output"))
      (node (ref "R1") (pin "2") (pinfunction "2_2") (pintype "passive"))
      (node (ref "Y1") (pin "1") (pinfunction "1_1") (pintype "passive"))
    )
    (net (code "116") (name "/XVCC") (class "Default")
      (node (ref "F1") (pin "2") (pinfunction "2_2") (pintype "passive"))
      (node (ref "J1") (pin "VBUS") (pinfunction "VBUS_VBUS") (pintype "power_in"))
    )
    (net (code "117") (name "GND") (class "Default")
      (node (ref "C1") (pin "2") (pinfunction "2_2") (pintype "passive"))
      (node (ref "C11") (pin "1") (pinfunction "1_1") (pintype "passive"))
      (node (ref "C12") (pin "1") (pinfunction "1_1") (pintype "passive"))
      (node (ref "C13") (pin "1") (pinfunction "1_1") (pintype "passive"))
      (node (ref "C14") (pin "2") (pinfunction "2_2") (pintype "passive"))
      (node (ref "C15") (pin "2") (pinfunction "2_2") (pintype "passive"))
      (node (ref "C16") (pin "1") (pinfunction "1_1") (pintype "passive"))
      (node (ref "C17") (pin "1") (pinfunction "1_1") (pintype "passive"))
      (node (ref "C18") (pin "1") (pinfunction "1_1") (pintype "passive"))
      (node (ref "C19") (pin "1") (pinfunction "1_1") (pintype "passive"))
      (node (ref "C2") (pin "1") (pinfunction "1_1") (pintype "passive"))
      (node (ref "C3") (pin "2") (pinfunction "2_2") (pintype "passive"))
      (node (ref "C4") (pin "2") (pinfunction "2_2") (pintype "passive"))
      (node (ref "C5") (pin "2") (pinfunction "2_2") (pintype "passive"))
      (node (ref "C6") (pin "2") (pinfunction "2_2") (pintype "passive"))
      (node (ref "C8") (pin "2") (pinfunction "2_2") (pintype "passive"))
      (node (ref "C9") (pin "2") (pinfunction "2_2") (pintype "passive"))
      (node (ref "GROUND") (pin "2") (pinfunction "2_2") (pintype "passive"))
      (node (ref "IC1") (pin "4") (pinfunction "V-_4") (pintype "power_in"))
      (node (ref "IC2") (pin "4") (pinfunction "V-_4") (pintype "power_in"))
      (node (ref "IC3") (pin "11") (pinfunction "GND_11") (pintype "power_in"))
      (node (ref "IC3") (pin "32") (pinfunction "GND1_32") (pintype "power_in"))
      (node (ref "IC3") (pin "62") (pinfunction "GND2_62") (pintype "power_in"))
      (node (ref "IC3") (pin "81") (pinfunction "GND3_81") (pintype "power_in"))
      (node (ref "IC3") (pin "99") (pinfunction "AGND_99") (pintype "power_in"))
      (node (ref "IC4") (pin "3") (pinfunction "GND_3") (pintype "power_in"))
      (node (ref "IC4") (pin "33") (pinfunction "PAD_33") (pintype "power_in"))
      (node (ref "IC5") (pin "4") (pinfunction "V-_4") (pintype "power_in"))
      (node (ref "IC6") (pin "2") (pinfunction "GND_2") (pintype "power_in"))
      (node (ref "IC7") (pin "4") (pinfunction "V-_4") (pintype "power_in"))
      (node (ref "IC8") (pin "4") (pinfunction "V-_4") (pintype "power_in"))
      (node (ref "IC9") (pin "4") (pinfunction "V-_4") (pintype "power_in"))
      (node (ref "ICSP") (pin "6") (pinfunction "6_6") (pintype "passive"))
      (node (ref "ICSP1") (pin "6") (pinfunction "6_6") (pintype "passive"))
      (node (ref "J2") (pin "2") (pinfunction "2_2") (pintype "passive"))
      (node (ref "JP2") (pin "12") (pinfunction "12_12") (pintype "passive"))
      (node (ref "JP2") (pin "3") (pinfunction "3_3") (pintype "passive"))
      (node (ref "JP2") (pin "4") (pinfunction "4_4") (pintype "passive"))
      (node (ref "JP2") (pin "9") (pinfunction "9_9") (pintype "passive"))
      (node (ref "L10") (pin "C") (pinfunction "C_C") (pintype "passive"))
      (node (ref "L11") (pin "C") (pinfunction "C_C") (pintype "passive"))
      (node (ref "L2") (pin "C") (pinfunction "C_C") (pintype "passive"))
      (node (ref "L3") (pin "C") (pinfunction "C_C") (pintype "passive"))
      (node (ref "L4") (pin "C") (pinfunction "C_C") (pintype "passive"))
      (node (ref "L5") (pin "C") (pinfunction "C_C") (pintype "passive"))
      (node (ref "L6") (pin "C") (pinfunction "C_C") (pintype "passive"))
      (node (ref "L7") (pin "C") (pinfunction "C_C") (pintype "passive"))
      (node (ref "L8") (pin "C") (pinfunction "C_C") (pintype "passive"))
      (node (ref "L9") (pin "C") (pinfunction "C_C") (pintype "passive"))
      (node (ref "ON") (pin "C") (pinfunction "C_C") (pintype "passive"))
      (node (ref "PAD2") (pin "1") (pinfunction "P_1") (pintype "passive"))
      (node (ref "RESET") (pin "1") (pinfunction "1_1") (pintype "passive"))
      (node (ref "RESET") (pin "2") (pinfunction "2_2") (pintype "passive"))
      (node (ref "RN11") (pin "1") (pinfunction "1_1") (pintype "passive"))
      (node (ref "RN11") (pin "2") (pinfunction "1_2") (pintype "passive"))
      (node (ref "RN11") (pin "3") (pinfunction "1_3") (pintype "passive"))
      (node (ref "RN11") (pin "4") (pinfunction "1_4") (pintype "passive"))
      (node (ref "RN3") (pin "5") (pinfunction "2_5") (pintype "passive"))
      (node (ref "RN5") (pin "4") (pinfunction "1_4") (pintype "passive"))
      (node (ref "RPI-ZERO") (pin "14") (pinfunction "14_14") (pintype "passive"))
      (node (ref "RPI-ZERO") (pin "20") (pinfunction "20_20") (pintype "passive"))
      (node (ref "RPI-ZERO") (pin "25") (pinfunction "25_25") (pintype "passive"))
      (node (ref "RPI-ZERO") (pin "30") (pinfunction "30_30") (pintype "passive"))
      (node (ref "RPI-ZERO") (pin "34") (pinfunction "34_34") (pintype "passive"))
      (node (ref "RPI-ZERO") (pin "39") (pinfunction "39_39") (pintype "passive"))
      (node (ref "RPI-ZERO") (pin "6") (pinfunction "6_6") (pintype "passive"))
      (node (ref "RPI-ZERO") (pin "9") (pinfunction "9_9") (pintype "passive"))
      (node (ref "Y1") (pin "2") (pinfunction "2_2") (pintype "passive"))
    )
    (net (code "118") (name "Net-(IC1A--IN)") (class "Default")
      (node (ref "IC1") (pin "1") (pinfunction "OUT_1") (pintype "output"))
      (node (ref "IC1") (pin "2") (pinfunction "-IN_2") (pintype "input"))
      (node (ref "RN1") (pin "2") (pinfunction "1_2") (pintype "passive"))
    )
    (net (code "119") (name "Net-(IC1B--IN)") (class "Default")
      (node (ref "IC1") (pin "6") (pinfunction "-IN_6") (pintype "input"))
      (node (ref "IC1") (pin "7") (pinfunction "OUT_7") (pintype "output"))
      (node (ref "RN1") (pin "1") (pinfunction "1_1") (pintype "passive"))
    )
    (net (code "120") (name "Net-(IC2A--IN)") (class "Default")
      (node (ref "IC2") (pin "1") (pinfunction "OUT_1") (pintype "output"))
      (node (ref "IC2") (pin "2") (pinfunction "-IN_2") (pintype "input"))
      (node (ref "RN6") (pin "8") (pinfunction "2_8") (pintype "passive"))
    )
    (net (code "121") (name "Net-(IC2B--IN)") (class "Default")
      (node (ref "IC2") (pin "6") (pinfunction "-IN_6") (pintype "input"))
      (node (ref "IC2") (pin "7") (pinfunction "OUT_7") (pintype "output"))
      (node (ref "RN6") (pin "7") (pinfunction "2_7") (pintype "passive"))
    )
    (net (code "122") (name "Net-(IC5A--IN)") (class "Default")
      (node (ref "IC5") (pin "1") (pinfunction "OUT_1") (pintype "output"))
      (node (ref "IC5") (pin "2") (pinfunction "-IN_2") (pintype "input"))
      (node (ref "RN8") (pin "1") (pinfunction "1_1") (pintype "passive"))
    )
    (net (code "123") (name "Net-(IC5B--IN)") (class "Default")
      (node (ref "IC5") (pin "6") (pinfunction "-IN_6") (pintype "input"))
      (node (ref "IC5") (pin "7") (pinfunction "OUT_7") (pintype "output"))
      (node (ref "RN8") (pin "2") (pinfunction "1_2") (pintype "passive"))
    )
    (net (code "124") (name "Net-(IC8A--IN)") (class "Default")
      (node (ref "IC8") (pin "1") (pinfunction "OUT_1") (pintype "output"))
      (node (ref "IC8") (pin "2") (pinfunction "-IN_2") (pintype "input"))
      (node (ref "RN9") (pin "8") (pinfunction "2_8") (pintype "passive"))
    )
    (net (code "125") (name "Net-(IC8B--IN)") (class "Default")
      (node (ref "IC8") (pin "6") (pinfunction "-IN_6") (pintype "input"))
      (node (ref "IC8") (pin "7") (pinfunction "OUT_7") (pintype "output"))
      (node (ref "RN9") (pin "7") (pinfunction "2_7") (pintype "passive"))
    )
    (net (code "126") (name "Net-(IC9A--IN)") (class "Default")
      (node (ref "IC9") (pin "1") (pinfunction "OUT_1") (pintype "output"))
      (node (ref "IC9") (pin "2") (pinfunction "-IN_2") (pintype "input"))
      (node (ref "RN10") (pin "8") (pinfunction "2_8") (pintype "passive"))
    )
    (net (code "127") (name "Net-(IC9B--IN)") (class "Default")
      (node (ref "IC9") (pin "6") (pinfunction "-IN_6") (pintype "input"))
      (node (ref "IC9") (pin "7") (pinfunction "OUT_7") (pintype "output"))
      (node (ref "RN10") (pin "7") (pinfunction "2_7") (pintype "passive"))
    )
    (net (code "128") (name "Net-(L4-PadA)") (class "Default")
      (node (ref "L4") (pin "A") (pinfunction "A_A") (pintype "passive"))
      (node (ref "RN6") (pin "1") (pinfunction "1_1") (pintype "passive"))
    )
    (net (code "129") (name "Net-(L8-PadA)") (class "Default")
      (node (ref "L8") (pin "A") (pinfunction "A_A") (pintype "passive"))
      (node (ref "RN9") (pin "1") (pinfunction "1_1") (pintype "passive"))
    )
    (net (code "130") (name "Net-(L10-PadA)") (class "Default")
      (node (ref "L10") (pin "A") (pinfunction "A_A") (pintype "passive"))
      (node (ref "RN10") (pin "1") (pinfunction "1_1") (pintype "passive"))
    )
    (net (code "131") (name "Net-(RN1A-2)") (class "Default")
      (node (ref "L3") (pin "A") (pinfunction "A_A") (pintype "passive"))
      (node (ref "RN1") (pin "8") (pinfunction "2_8") (pintype "passive"))
    )
    (net (code "132") (name "Net-(RN1B-2)") (class "Default")
      (node (ref "L2") (pin "A") (pinfunction "A_A") (pintype "passive"))
      (node (ref "RN1") (pin "7") (pinfunction "2_7") (pintype "passive"))
    )
    (net (code "133") (name "Net-(RN3A-2)") (class "Default")
      (node (ref "ON") (pin "A") (pinfunction "A_A") (pintype "passive"))
      (node (ref "RN3") (pin "8") (pinfunction "2_8") (pintype "passive"))
    )
    (net (code "134") (name "Net-(RN4C-1)") (class "Default")
      (node (ref "RN4") (pin "3") (pinfunction "1_3") (pintype "passive"))
      (node (ref "TX") (pin "A") (pinfunction "A_A") (pintype "passive"))
    )
    (net (code "135") (name "Net-(RN4D-1)") (class "Default")
      (node (ref "RN4") (pin "4") (pinfunction "1_4") (pintype "passive"))
      (node (ref "RX") (pin "A") (pinfunction "A_A") (pintype "passive"))
    )
    (net (code "136") (name "Net-(RN6B-1)") (class "Default")
      (node (ref "L5") (pin "A") (pinfunction "A_A") (pintype "passive"))
      (node (ref "RN6") (pin "2") (pinfunction "1_2") (pintype "passive"))
    )
    (net (code "137") (name "Net-(RN8A-2)") (class "Default")
      (node (ref "L6") (pin "A") (pinfunction "A_A") (pintype "passive"))
      (node (ref "RN8") (pin "8") (pinfunction "2_8") (pintype "passive"))
    )
    (net (code "138") (name "Net-(RN8B-2)") (class "Default")
      (node (ref "L7") (pin "A") (pinfunction "A_A") (pintype "passive"))
      (node (ref "RN8") (pin "7") (pinfunction "2_7") (pintype "passive"))
    )
    (net (code "139") (name "Net-(RN9B-1)") (class "Default")
      (node (ref "L9") (pin "A") (pinfunction "A_A") (pintype "passive"))
      (node (ref "RN9") (pin "2") (pinfunction "1_2") (pintype "passive"))
    )
    (net (code "140") (name "Net-(RN10B-1)") (class "Default")
      (node (ref "L11") (pin "A") (pinfunction "A_A") (pintype "passive"))
      (node (ref "RN10") (pin "2") (pinfunction "1_2") (pintype "passive"))
    )
    (net (code "141") (name "unconnected-(IC3-(CLKO{slash}ICP3{slash}INT7)PE7-Pad9)") (class "Default")
      (node (ref "IC3") (pin "9") (pinfunction "(CLKO/ICP3/INT7)PE7_9") (pintype "bidirectional"))
    )
    (net (code "142") (name "unconnected-(IC3-(ICP1)PD4-Pad47)") (class "Default")
      (node (ref "IC3") (pin "47") (pinfunction "(ICP1)PD4_47") (pintype "bidirectional"))
    )
    (net (code "143") (name "unconnected-(IC3-(OC0B)PG5-Pad1)") (class "Default")
      (node (ref "IC3") (pin "1") (pinfunction "(OC0B)PG5_1") (pintype "bidirectional"))
    )
    (net (code "144") (name "unconnected-(IC3-(OC3A{slash}AIN1)PE3-Pad5)") (class "Default")
      (node (ref "IC3") (pin "5") (pinfunction "(OC3A/AIN1)PE3_5") (pintype "bidirectional"))
    )
    (net (code "145") (name "unconnected-(IC3-(OC3B{slash}INT4)PE4-Pad6)") (class "Default")
      (node (ref "IC3") (pin "6") (pinfunction "(OC3B/INT4)PE4_6") (pintype "bidirectional"))
    )
    (net (code "146") (name "unconnected-(IC3-(OC3C{slash}INT5)PE5-Pad7)") (class "Default")
      (node (ref "IC3") (pin "7") (pinfunction "(OC3C/INT5)PE5_7") (pintype "bidirectional"))
    )
    (net (code "147") (name "unconnected-(IC3-(T1)PD6-Pad49)") (class "Default")
      (node (ref "IC3") (pin "49") (pinfunction "(T1)PD6_49") (pintype "bidirectional"))
    )
    (net (code "148") (name "unconnected-(IC3-(T3{slash}INT6)PE6-Pad8)") (class "Default")
      (node (ref "IC3") (pin "8") (pinfunction "(T3/INT6)PE6_8") (pintype "bidirectional"))
    )
    (net (code "149") (name "unconnected-(IC3-(TOSC1)PG4-Pad29)") (class "Default")
      (node (ref "IC3") (pin "29") (pinfunction "(TOSC1)PG4_29") (pintype "bidirectional"))
    )
    (net (code "150") (name "unconnected-(IC3-(TOSC2)PG3-Pad28)") (class "Default")
      (node (ref "IC3") (pin "28") (pinfunction "(TOSC2)PG3_28") (pintype "bidirectional"))
    )
    (net (code "151") (name "unconnected-(IC3-(XCK0{slash}AIN0)PE2-Pad4)") (class "Default")
      (node (ref "IC3") (pin "4") (pinfunction "(XCK0/AIN0)PE2_4") (pintype "bidirectional"))
    )
    (net (code "152") (name "unconnected-(IC3-(XCK1)PD5-Pad48)") (class "Default")
      (node (ref "IC3") (pin "48") (pinfunction "(XCK1)PD5_48") (pintype "bidirectional"))
    )
    (net (code "153") (name "unconnected-(IC3-PH2(XCK2)-Pad14)") (class "Default")
      (node (ref "IC3") (pin "14") (pinfunction "PH2(XCK2)_14") (pintype "bidirectional"))
    )
    (net (code "154") (name "unconnected-(IC3-PH7(T4)-Pad27)") (class "Default")
      (node (ref "IC3") (pin "27") (pinfunction "PH7(T4)_27") (pintype "bidirectional"))
    )
    (net (code "155") (name "unconnected-(IC3-PJ2(XCK3{slash}PCINT11)-Pad65)") (class "Default")
      (node (ref "IC3") (pin "65") (pinfunction "PJ2(XCK3/PCINT11)_65") (pintype "bidirectional"))
    )
    (net (code "156") (name "unconnected-(IC3-PJ3(PCINT12)-Pad66)") (class "Default")
      (node (ref "IC3") (pin "66") (pinfunction "PJ3(PCINT12)_66") (pintype "bidirectional"))
    )
    (net (code "157") (name "unconnected-(IC3-PJ4(PCINT13)-Pad67)") (class "Default")
      (node (ref "IC3") (pin "67") (pinfunction "PJ4(PCINT13)_67") (pintype "bidirectional"))
    )
    (net (code "158") (name "unconnected-(IC3-PJ5(PCINT14)-Pad68)") (class "Default")
      (node (ref "IC3") (pin "68") (pinfunction "PJ5(PCINT14)_68") (pintype "bidirectional"))
    )
    (net (code "159") (name "unconnected-(IC3-PJ6(PCINT15)-Pad69)") (class "Default")
      (node (ref "IC3") (pin "69") (pinfunction "PJ6(PCINT15)_69") (pintype "bidirectional"))
    )
    (net (code "160") (name "unconnected-(IC3-PJ7-Pad79)") (class "Default")
      (node (ref "IC3") (pin "79") (pinfunction "PJ7_79") (pintype "bidirectional"))
    )
    (net (code "161") (name "unconnected-(IC3-PK0(ADC8{slash}PCINT16)-Pad89)") (class "Default")
      (node (ref "IC3") (pin "89") (pinfunction "PK0(ADC8/PCINT16)_89") (pintype "bidirectional"))
    )
    (net (code "162") (name "unconnected-(IC3-PK1(ADC9{slash}PCINT17)-Pad88)") (class "Default")
      (node (ref "IC3") (pin "88") (pinfunction "PK1(ADC9/PCINT17)_88") (pintype "bidirectional"))
    )
    (net (code "163") (name "unconnected-(IC3-PK2(ADC10{slash}PCINT18)-Pad87)") (class "Default")
      (node (ref "IC3") (pin "87") (pinfunction "PK2(ADC10/PCINT18)_87") (pintype "bidirectional"))
    )
    (net (code "164") (name "unconnected-(IC3-PK3(ADC11{slash}PCINT19)-Pad86)") (class "Default")
      (node (ref "IC3") (pin "86") (pinfunction "PK3(ADC11/PCINT19)_86") (pintype "bidirectional"))
    )
    (net (code "165") (name "unconnected-(IC3-PK4(ADC12{slash}PCINT20)-Pad85)") (class "Default")
      (node (ref "IC3") (pin "85") (pinfunction "PK4(ADC12/PCINT20)_85") (pintype "bidirectional"))
    )
    (net (code "166") (name "unconnected-(IC3-PK5(ADC13{slash}PCINT21)-Pad84)") (class "Default")
      (node (ref "IC3") (pin "84") (pinfunction "PK5(ADC13/PCINT21)_84") (pintype "bidirectional"))
    )
    (net (code "167") (name "unconnected-(IC3-PK6(ADC14{slash}PCINT22)-Pad83)") (class "Default")
      (node (ref "IC3") (pin "83") (pinfunction "PK6(ADC14/PCINT22)_83") (pintype "bidirectional"))
    )
    (net (code "168") (name "unconnected-(IC3-PK7(ADC15{slash}PCINT23)-Pad82)") (class "Default")
      (node (ref "IC3") (pin "82") (pinfunction "PK7(ADC15/PCINT23)_82") (pintype "bidirectional"))
    )
    (net (code "169") (name "unconnected-(IC4-(AIN0{slash}INT1)PD1-Pad7)") (class "Default")
      (node (ref "IC4") (pin "7") (pinfunction "(AIN0/INT1)PD1_7") (pintype "bidirectional"))
    )
    (net (code "170") (name "unconnected-(IC4-(AIN2{slash}PCINT11)PC2-Pad5)") (class "Default")
      (node (ref "IC4") (pin "5") (pinfunction "(AIN2/PCINT11)PC2_5") (pintype "bidirectional"))
    )
    (net (code "171") (name "unconnected-(IC4-(INT4{slash}ICP1{slash}CLK0)PC7-Pad22)") (class "Default")
      (node (ref "IC4") (pin "22") (pinfunction "(INT4/ICP1/CLK0)PC7_22") (pintype "bidirectional"))
    )
    (net (code "172") (name "unconnected-(IC4-(OC0B{slash}INT0)PD0-Pad6)") (class "Default")
      (node (ref "IC4") (pin "6") (pinfunction "(OC0B/INT0)PD0_6") (pintype "bidirectional"))
    )
    (net (code "173") (name "unconnected-(IC4-(OC1A{slash}PCINT8)PC6-Pad23)") (class "Default")
      (node (ref "IC4") (pin "23") (pinfunction "(OC1A/PCINT8)PC6_23") (pintype "bidirectional"))
    )
    (net (code "174") (name "unconnected-(IC4-(PCINT9{slash}OC1B)PC5-Pad25)") (class "Default")
      (node (ref "IC4") (pin "25") (pinfunction "(PCINT9/OC1B)PC5_25") (pintype "bidirectional"))
    )
    (net (code "175") (name "unconnected-(IC4-(PCINT10)PC4-Pad26)") (class "Default")
      (node (ref "IC4") (pin "26") (pinfunction "(PCINT10)PC4_26") (pintype "bidirectional"))
    )
    (net (code "176") (name "unconnected-(IC4-(RTS{slash}AIN5{slash}INT6)PD6-Pad12)") (class "Default")
      (node (ref "IC4") (pin "12") (pinfunction "(RTS/AIN5/INT6)PD6_12") (pintype "bidirectional"))
    )
    (net (code "177") (name "unconnected-(IC4-(SS{slash}PCINT0)PB0-Pad14)") (class "Default")
      (node (ref "IC4") (pin "14") (pinfunction "(SS/PCINT0)PB0_14") (pintype "bidirectional"))
    )
    (net (code "178") (name "unconnected-(IC6-NC{slash}FB-Pad4)") (class "Default")
      (node (ref "IC6") (pin "4") (pinfunction "NC/FB_4") (pintype "passive"))
    )
    (net (code "179") (name "unconnected-(J1-PadID)") (class "Default")
      (node (ref "J1") (pin "ID") (pinfunction "ID_ID") (pintype "bidirectional"))
    )
    (net (code "180") (name "unconnected-(RN1C-1-Pad3)") (class "Default")
      (node (ref "RN1") (pin "3") (pinfunction "1_3") (pintype "passive"))
    )
    (net (code "181") (name "unconnected-(RN1C-2-Pad6)") (class "Default")
      (node (ref "RN1") (pin "6") (pinfunction "2_6") (pintype "passive"))
    )
    (net (code "182") (name "unconnected-(RN1D-1-Pad4)") (class "Default")
      (node (ref "RN1") (pin "4") (pinfunction "1_4") (pintype "passive"))
    )
    (net (code "183") (name "unconnected-(RN1D-2-Pad5)") (class "Default")
      (node (ref "RN1") (pin "5") (pinfunction "2_5") (pintype "passive"))
    )
    (net (code "184") (name "unconnected-(RN2B-1-Pad2)") (class "Default")
      (node (ref "RN2") (pin "2") (pinfunction "1_2") (pintype "passive"))
    )
    (net (code "185") (name "unconnected-(RN2B-2-Pad7)") (class "Default")
      (node (ref "RN2") (pin "7") (pinfunction "2_7") (pintype "passive"))
    )
    (net (code "186") (name "unconnected-(RN2C-1-Pad3)") (class "Default")
      (node (ref "RN2") (pin "3") (pinfunction "1_3") (pintype "passive"))
    )
    (net (code "187") (name "unconnected-(RN2C-2-Pad6)") (class "Default")
      (node (ref "RN2") (pin "6") (pinfunction "2_6") (pintype "passive"))
    )
    (net (code "188") (name "unconnected-(RN3C-1-Pad3)") (class "Default")
      (node (ref "RN3") (pin "3") (pinfunction "1_3") (pintype "passive"))
    )
    (net (code "189") (name "unconnected-(RN3C-2-Pad6)") (class "Default")
      (node (ref "RN3") (pin "6") (pinfunction "2_6") (pintype "passive"))
    )
    (net (code "190") (name "unconnected-(RN6C-1-Pad3)") (class "Default")
      (node (ref "RN6") (pin "3") (pinfunction "1_3") (pintype "passive"))
    )
    (net (code "191") (name "unconnected-(RN6C-2-Pad6)") (class "Default")
      (node (ref "RN6") (pin "6") (pinfunction "2_6") (pintype "passive"))
    )
    (net (code "192") (name "unconnected-(RN6D-1-Pad4)") (class "Default")
      (node (ref "RN6") (pin "4") (pinfunction "1_4") (pintype "passive"))
    )
    (net (code "193") (name "unconnected-(RN6D-2-Pad5)") (class "Default")
      (node (ref "RN6") (pin "5") (pinfunction "2_5") (pintype "passive"))
    )
    (net (code "194") (name "unconnected-(RN8C-1-Pad3)") (class "Default")
      (node (ref "RN8") (pin "3") (pinfunction "1_3") (pintype "passive"))
    )
    (net (code "195") (name "unconnected-(RN8C-2-Pad6)") (class "Default")
      (node (ref "RN8") (pin "6") (pinfunction "2_6") (pintype "passive"))
    )
    (net (code "196") (name "unconnected-(RN8D-1-Pad4)") (class "Default")
      (node (ref "RN8") (pin "4") (pinfunction "1_4") (pintype "passive"))
    )
    (net (code "197") (name "unconnected-(RN8D-2-Pad5)") (class "Default")
      (node (ref "RN8") (pin "5") (pinfunction "2_5") (pintype "passive"))
    )
    (net (code "198") (name "unconnected-(RN9C-1-Pad3)") (class "Default")
      (node (ref "RN9") (pin "3") (pinfunction "1_3") (pintype "passive"))
    )
    (net (code "199") (name "unconnected-(RN9C-2-Pad6)") (class "Default")
      (node (ref "RN9") (pin "6") (pinfunction "2_6") (pintype "passive"))
    )
    (net (code "200") (name "unconnected-(RN9D-1-Pad4)") (class "Default")
      (node (ref "RN9") (pin "4") (pinfunction "1_4") (pintype "passive"))
    )
    (net (code "201") (name "unconnected-(RN9D-2-Pad5)") (class "Default")
      (node (ref "RN9") (pin "5") (pinfunction "2_5") (pintype "passive"))
    )
    (net (code "202") (name "unconnected-(RN10C-1-Pad3)") (class "Default")
      (node (ref "RN10") (pin "3") (pinfunction "1_3") (pintype "passive"))
    )
    (net (code "203") (name "unconnected-(RN10C-2-Pad6)") (class "Default")
      (node (ref "RN10") (pin "6") (pinfunction "2_6") (pintype "passive"))
    )
    (net (code "204") (name "unconnected-(RN10D-1-Pad4)") (class "Default")
      (node (ref "RN10") (pin "4") (pinfunction "1_4") (pintype "passive"))
    )
    (net (code "205") (name "unconnected-(RN10D-2-Pad5)") (class "Default")
      (node (ref "RN10") (pin "5") (pinfunction "2_5") (pintype "passive"))
    )
  )
)
